# remote-connection-board-v2.net
KiCad netlist of a schematic drawn in EAGLE
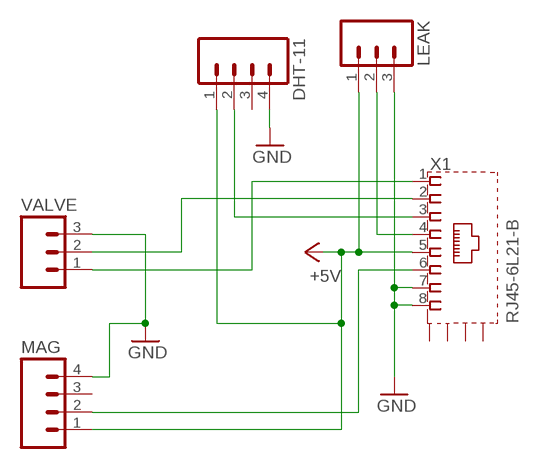
[diagram p0: schematic, sheet 1]

(export (version "E")
  (design (tool "Eeschema 10.0.6"))
  (components
    (comp (ref "DHT-11")
      (value "M04")
      (footprint "eagle-import:04P")
      (libsource (lib "eagle-import") (part "M04"))
    )
    (comp (ref "LEAK")
      (value "M03")
      (footprint "eagle-import:03P")
      (libsource (lib "eagle-import") (part "M03"))
    )
    (comp (ref "MAG")
      (value "M04")
      (footprint "eagle-import:04P")
      (libsource (lib "eagle-import") (part "M04"))
    )
    (comp (ref "VALVE")
      (value "M03")
      (footprint "eagle-import:03P")
      (libsource (lib "eagle-import") (part "M03"))
    )
    (comp (ref "X1")
      (value "RJ45-6L21-B")
      (footprint "eagle-import:RJ45-SHIELD1")
      (libsource (lib "eagle-import") (part "RJ4521-B-6L"))
    )
  )
  (nets
    (net (code "1") (name "+5V") (class "Default")
      (node (ref "DHT-11") (pin "1") (pinfunction "1_1") (pintype "passive"))
      (node (ref "LEAK") (pin "1") (pinfunction "1_1") (pintype "passive"))
      (node (ref "MAG") (pin "1") (pinfunction "1_1") (pintype "passive"))
      (node (ref "X1") (pin "5") (pinfunction "5_5") (pintype "passive"))
    )
    (net (code "2") (name "GND") (class "Default")
      (node (ref "DHT-11") (pin "4") (pinfunction "4_4") (pintype "passive"))
      (node (ref "LEAK") (pin "3") (pinfunction "3_3") (pintype "passive"))
      (node (ref "MAG") (pin "4") (pinfunction "4_4") (pintype "passive"))
      (node (ref "VALVE") (pin "3") (pinfunction "3_3") (pintype "passive"))
      (node (ref "X1") (pin "7") (pinfunction "7_7") (pintype "passive"))
      (node (ref "X1") (pin "8") (pinfunction "8_8") (pintype "passive"))
    )
    (net (code "3") (name "Net-(DHT-11-Pad2)") (class "Default")
      (node (ref "DHT-11") (pin "2") (pinfunction "2_2") (pintype "passive"))
      (node (ref "X1") (pin "3") (pinfunction "3_3") (pintype "passive"))
    )
    (net (code "4") (name "Net-(LEAK-Pad2)") (class "Default")
      (node (ref "LEAK") (pin "2") (pinfunction "2_2") (pintype "passive"))
      (node (ref "X1") (pin "4") (pinfunction "4_4") (pintype "passive"))
    )
    (net (code "5") (name "Net-(MAG-Pad2)") (class "Default")
      (node (ref "MAG") (pin "2") (pinfunction "2_2") (pintype "passive"))
      (node (ref "X1") (pin "6") (pinfunction "6_6") (pintype "passive"))
    )
    (net (code "6") (name "Net-(VALVE-Pad1)") (class "Default")
      (node (ref "VALVE") (pin "1") (pinfunction "1_1") (pintype "passive"))
      (node (ref "X1") (pin "1") (pinfunction "1_1") (pintype "passive"))
    )
    (net (code "7") (name "Net-(VALVE-Pad2)") (class "Default")
      (node (ref "VALVE") (pin "2") (pinfunction "2_2") (pintype "passive"))
      (node (ref "X1") (pin "2") (pinfunction "2_2") (pintype "passive"))
    )
    (net (code "8") (name "unconnected-(DHT-11-Pad3)") (class "Default")
      (node (ref "DHT-11") (pin "3") (pinfunction "3_3") (pintype "passive"))
    )
    (net (code "9") (name "unconnected-(MAG-Pad3)") (class "Default")
      (node (ref "MAG") (pin "3") (pinfunction "3_3") (pintype "passive"))
    )
    (net (code "10") (name "unconnected-(X1-S-PadS1)") (class "Default")
      (node (ref "X1") (pin "S1") (pinfunction "S_S1") (pintype "passive"))
    )
    (net (code "11") (name "unconnected-(X1-S-PadS2)") (class "Default")
      (node (ref "X1") (pin "S2") (pinfunction "S_S2") (pintype "passive"))
    )
    (net (code "12") (name "unconnected-(X1-S-PadS3)") (class "Default")
      (node (ref "X1") (pin "S3") (pinfunction "S_S3") (pintype "passive"))
    )
    (net (code "13") (name "unconnected-(X1-S-PadS4)") (class "Default")
      (node (ref "X1") (pin "S4") (pinfunction "S_S4") (pintype "passive"))
    )
  )
)
